# supply1.net
KiCad netlist of a schematic drawn in Altium Designer
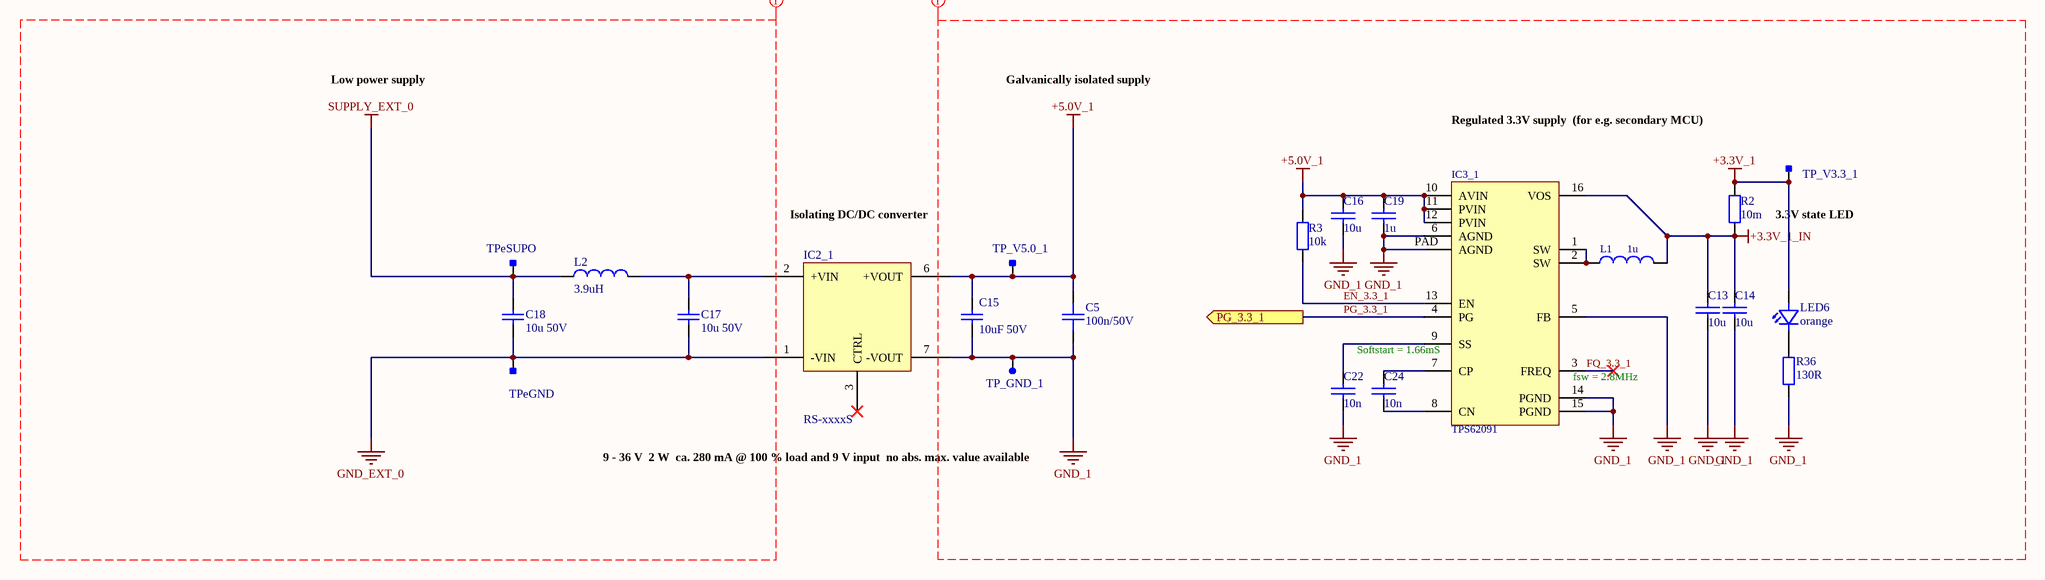
[diagram p0: supply1.SchDoc]

(export (version "E")
  (design (tool "Eeschema 10.0.6"))
  (components
    (comp (ref "C5")
      (value "100n/50V")
      (footprint "0603C")
      (description "MLCC")
      (fields (field (name "PART NUMBER") "gen_C_ceramic_100n_50V_X7R_0603"))
      (libsource (lib "OE750") (part "C"))
    )
    (comp (ref "C13")
      (value "10u")
      (footprint "0603C")
      (description "10u 20% 6.3V 0603 X5R ceramic capacitor, RoHS compliant")
      (libsource (lib "*") (part "CAP"))
    )
    (comp (ref "C14")
      (value "10u")
      (footprint "0603C")
      (description "10u 20% 6.3V 0603 X5R ceramic capacitor, RoHS compliant")
      (libsource (lib "*") (part "CAP"))
    )
    (comp (ref "C15")
      (value "10uF 50V")
      (footprint "CAPC3225X279X50LL20T25")
      (description "Multilayer Ceramic Capacitor, 50 V, -55 to 125 degC, 2-Pin SMD (1210), RoHS, Tape and Reel")
      (fields (field (name "TOLERANCE") "10%") (field (name "MANUFACTURER") "AVX"))
      (libsource (lib "Altium Content Vault") (part "CAP-NP-2"))
    )
    (comp (ref "C16")
      (value "10u")
      (footprint "0805C")
      (description "10u 20% 6.3V 0603 X5R ceramic capacitor, RoHS compliant")
      (libsource (lib "*") (part "CAP"))
    )
    (comp (ref "C17")
      (value "10u 50V")
      (footprint "CAPC3225X279X50LL20T25")
      (description "Multilayer Ceramic Capacitor, 50 V, -55 to 125 degC, 2-Pin SMD (1210), RoHS, Tape and Reel")
      (fields (field (name "TOLERANCE") "10%") (field (name "MANUFACTURER") "AVX"))
      (libsource (lib "Altium Content Vault") (part "CAP-NP-2"))
    )
    (comp (ref "C18")
      (value "10u 50V")
      (footprint "CAPC3225X279X50LL20T25")
      (description "Multilayer Ceramic Capacitor, 50 V, -55 to 125 degC, 2-Pin SMD (1210), RoHS, Tape and Reel")
      (fields (field (name "TOLERANCE") "10%") (field (name "MANUFACTURER") "AVX"))
      (libsource (lib "Altium Content Vault") (part "CAP-NP-2"))
    )
    (comp (ref "C19")
      (value "1u")
      (footprint "0603C")
      (description "10u 20% 6.3V 0603 X5R ceramic capacitor, RoHS compliant")
      (libsource (lib "*") (part "CAP"))
    )
    (comp (ref "C22")
      (value "10n")
      (footprint "0603C")
      (description "10u 20% 6.3V 0603 X5R ceramic capacitor, RoHS compliant")
      (libsource (lib "*") (part "CAP"))
    )
    (comp (ref "C24")
      (value "10n")
      (footprint "0603C")
      (description "10u 20% 6.3V 0603 X5R ceramic capacitor, RoHS compliant")
      (libsource (lib "*") (part "CAP"))
    )
    (comp (ref "IC2_1")
      (value "RS-xxxxS")
      (footprint "RECOM_RS-S_D")
      (description "Isolating DC/DC Converter")
      (fields (field (name "PART NUMBER") "Recom_RS-2405SZ/H3") (field (name "MANUFACTURER") "Recom"))
      (libsource (lib "OE750") (part "RS-xxxxS"))
    )
    (comp (ref "IC3_1")
      (value "TPS62091")
      (footprint "QFN-16-TI")
      (libsource (lib "Schematic") (part "TPS62090"))
    )
    (comp (ref "L1")
      (value "1u")
      (footprint "WE-LQS")
      (description "1u 3.8A 25mR 20% IFSC-1515 inductor, RoHS compliant")
      (libsource (lib "*") (part "INDUCTOR"))
    )
    (comp (ref "L2")
      (value "3.9uH")
      (footprint "INDC4532")
      (description "3.9µH Unshielded Wirewound Inductor 1.32A 140mOhm Max 1812 (4532 Metric)")
      (fields
        (field (name "PARTNUMBER") "RLS-397")
        (field (name "Comment") "FIXED IND 3.9UH 1.32A 140MOHM SM")
        (field (name "PUBLISHER") "Altium Limited")
      )
      (libsource (lib "Miscellaneous Devices") (part "Inductor"))
    )
    (comp (ref "LED6")
      (value "orange")
      (footprint "LEDC1608X07N")
      (description "LED")
      (fields (field (name "PART NUMBER") "gen_LED_0603_orange"))
      (libsource (lib "OE750") (part "D_LED"))
    )
    (comp (ref "R2")
      (value "10m")
      (footprint "0805R")
      (description "Resistor")
      (libsource (lib "") (part "Res2_1"))
    )
    (comp (ref "R3")
      (value "10k")
      (footprint "0603R")
      (description "Resistor")
      (libsource (lib "Miscellaneous Devices") (part "Res2"))
    )
    (comp (ref "R36")
      (value "130R")
      (footprint "0603R")
      (description "SMD Resistor 130R 0603")
      (fields (field (name "PART NUMBER") "gen_R_130R_0603") (field (name "TOLERANCE") "1%"))
      (libsource (lib "OE750") (part "R"))
    )
    (comp (ref "TPeGND")
      (value "Testpoint_Square")
      (footprint "Testpoint_S1")
      (description "Testpoint, square")
      (libsource (lib "OE750") (part "Testpoint_Square"))
    )
    (comp (ref "TPeSUPO")
      (value "Testpoint_Square")
      (footprint "Testpoint_S1")
      (description "Testpoint, square")
      (libsource (lib "OE750") (part "Testpoint_Square"))
    )
    (comp (ref "TP_GND_1")
      (value "Testpoint_Round")
      (footprint "Testpoint_D1V")
      (description "Testpoint, Via, round")
      (fields (field (name "PART NUMBER") "Testpoint_Round_Via"))
      (libsource (lib "OE750") (part "Testpoint_Round"))
    )
    (comp (ref "TP_V3.3_1")
      (value "Testpoint_Square")
      (footprint "Testpoint_S1")
      (description "Testpoint, square")
      (libsource (lib "OE750") (part "Testpoint_Square"))
    )
    (comp (ref "TP_V5.0_1")
      (value "Testpoint_Square")
      (footprint "Testpoint_S1")
      (description "Testpoint, square")
      (libsource (lib "OE750") (part "Testpoint_Square"))
    )
  )
  (nets
    (net (code "1") (name "+3.3V_1") (class "Default")
      (node (ref "LED6") (pin "2") (pinfunction "A_2") (pintype "passive"))
      (node (ref "R2") (pin "1") (pinfunction "1_1") (pintype "passive"))
      (node (ref "TP_V3.3_1") (pin "1") (pinfunction "1_1") (pintype "passive"))
    )
    (net (code "2") (name "+3.3V_1_IN") (class "Default")
      (node (ref "C13") (pin "1") (pintype "passive"))
      (node (ref "C14") (pin "1") (pintype "passive"))
      (node (ref "IC3_1") (pin "16") (pinfunction "VOS_16") (pintype "passive"))
      (node (ref "L1") (pin "2") (pinfunction "2_2") (pintype "passive"))
      (node (ref "R2") (pin "2") (pinfunction "2_2") (pintype "passive"))
    )
    (net (code "3") (name "+5.0V_1") (class "Default")
      (node (ref "C15") (pin "2") (pinfunction "2_2") (pintype "passive"))
      (node (ref "C16") (pin "1") (pintype "passive"))
      (node (ref "C19") (pin "1") (pintype "passive"))
      (node (ref "C5") (pin "1") (pinfunction "1_1") (pintype "passive"))
      (node (ref "IC2_1") (pin "6") (pinfunction "+VOUT_6") (pintype "power_in"))
      (node (ref "IC3_1") (pin "10") (pinfunction "AVIN_10") (pintype "passive"))
      (node (ref "IC3_1") (pin "11") (pinfunction "PVIN_11") (pintype "passive"))
      (node (ref "IC3_1") (pin "12") (pinfunction "PVIN_12") (pintype "passive"))
      (node (ref "R3") (pin "2") (pinfunction "2_2") (pintype "passive"))
      (node (ref "TP_V5.0_1") (pin "1") (pinfunction "1_1") (pintype "passive"))
    )
    (net (code "4") (name "/EN_3.3_1") (class "Default")
      (node (ref "IC3_1") (pin "13") (pinfunction "EN_13") (pintype "passive"))
      (node (ref "R3") (pin "1") (pinfunction "1_1") (pintype "passive"))
    )
    (net (code "5") (name "/FQ_3.3_1") (class "Default")
      (node (ref "IC3_1") (pin "3") (pinfunction "FREQ_3") (pintype "passive+no_connect"))
    )
    (net (code "6") (name "/PG_3.3_1") (class "Default")
      (node (ref "IC3_1") (pin "4") (pinfunction "PG_4") (pintype "passive"))
    )
    (net (code "7") (name "GND_1") (class "Default")
      (node (ref "C13") (pin "2") (pintype "passive"))
      (node (ref "C14") (pin "2") (pintype "passive"))
      (node (ref "C15") (pin "1") (pinfunction "1_1") (pintype "passive"))
      (node (ref "C16") (pin "2") (pintype "passive"))
      (node (ref "C19") (pin "2") (pintype "passive"))
      (node (ref "C22") (pin "2") (pintype "passive"))
      (node (ref "C5") (pin "2") (pinfunction "2_2") (pintype "passive"))
      (node (ref "IC2_1") (pin "7") (pinfunction "-VOUT_7") (pintype "power_in"))
      (node (ref "IC3_1") (pin "14") (pinfunction "PGND_14") (pintype "passive"))
      (node (ref "IC3_1") (pin "15") (pinfunction "PGND_15") (pintype "passive"))
      (node (ref "IC3_1") (pin "5") (pinfunction "FB_5") (pintype "passive"))
      (node (ref "IC3_1") (pin "6") (pinfunction "AGND_6") (pintype "passive"))
      (node (ref "IC3_1") (pin "PAD") (pinfunction "AGND_PAD") (pintype "passive"))
      (node (ref "R36") (pin "2") (pinfunction "2_2") (pintype "passive"))
      (node (ref "TP_GND_1") (pin "1") (pinfunction "1_1") (pintype "passive"))
    )
    (net (code "8") (name "GND_EXT_0") (class "Default")
      (node (ref "C17") (pin "1") (pinfunction "1_1") (pintype "passive"))
      (node (ref "C18") (pin "1") (pinfunction "1_1") (pintype "passive"))
      (node (ref "IC2_1") (pin "1") (pinfunction "-VIN_1") (pintype "power_in"))
      (node (ref "TPeGND") (pin "1") (pinfunction "1_1") (pintype "passive"))
    )
    (net (code "9") (name "Net-(IC2_1-+VIN)") (class "Default")
      (node (ref "C17") (pin "2") (pinfunction "2_2") (pintype "passive"))
      (node (ref "IC2_1") (pin "2") (pinfunction "+VIN_2") (pintype "power_in"))
      (node (ref "L2") (pin "2") (pinfunction "2_2") (pintype "passive"))
    )
    (net (code "10") (name "Net-(IC3_1-CN)") (class "Default")
      (node (ref "C24") (pin "2") (pintype "passive"))
      (node (ref "IC3_1") (pin "8") (pinfunction "CN_8") (pintype "passive"))
    )
    (net (code "11") (name "Net-(IC3_1-CP)") (class "Default")
      (node (ref "C24") (pin "1") (pintype "passive"))
      (node (ref "IC3_1") (pin "7") (pinfunction "CP_7") (pintype "passive"))
    )
    (net (code "12") (name "Net-(IC3_1-SS)") (class "Default")
      (node (ref "C22") (pin "1") (pintype "passive"))
      (node (ref "IC3_1") (pin "9") (pinfunction "SS_9") (pintype "passive"))
    )
    (net (code "13") (name "Net-(IC3_1-SW-Pad1)") (class "Default")
      (node (ref "IC3_1") (pin "1") (pinfunction "SW_1") (pintype "passive"))
      (node (ref "IC3_1") (pin "2") (pinfunction "SW_2") (pintype "passive"))
      (node (ref "L1") (pin "1") (pinfunction "1_1") (pintype "passive"))
    )
    (net (code "14") (name "Net-(LED6-C)") (class "Default")
      (node (ref "LED6") (pin "1") (pinfunction "C_1") (pintype "passive"))
      (node (ref "R36") (pin "1") (pinfunction "1_1") (pintype "passive"))
    )
    (net (code "15") (name "SUPPLY_EXT_0") (class "Default")
      (node (ref "C18") (pin "2") (pinfunction "2_2") (pintype "passive"))
      (node (ref "L2") (pin "1") (pinfunction "1_1") (pintype "passive"))
      (node (ref "TPeSUPO") (pin "1") (pinfunction "1_1") (pintype "passive"))
    )
    (net (code "16") (name "unconnected-(IC2_1-CTRL-Pad3)") (class "Default")
      (node (ref "IC2_1") (pin "3") (pinfunction "CTRL_3") (pintype "passive+no_connect"))
    )
  )
)
